# Motercontroller.net
KiCad netlist of a schematic drawn in EAGLE
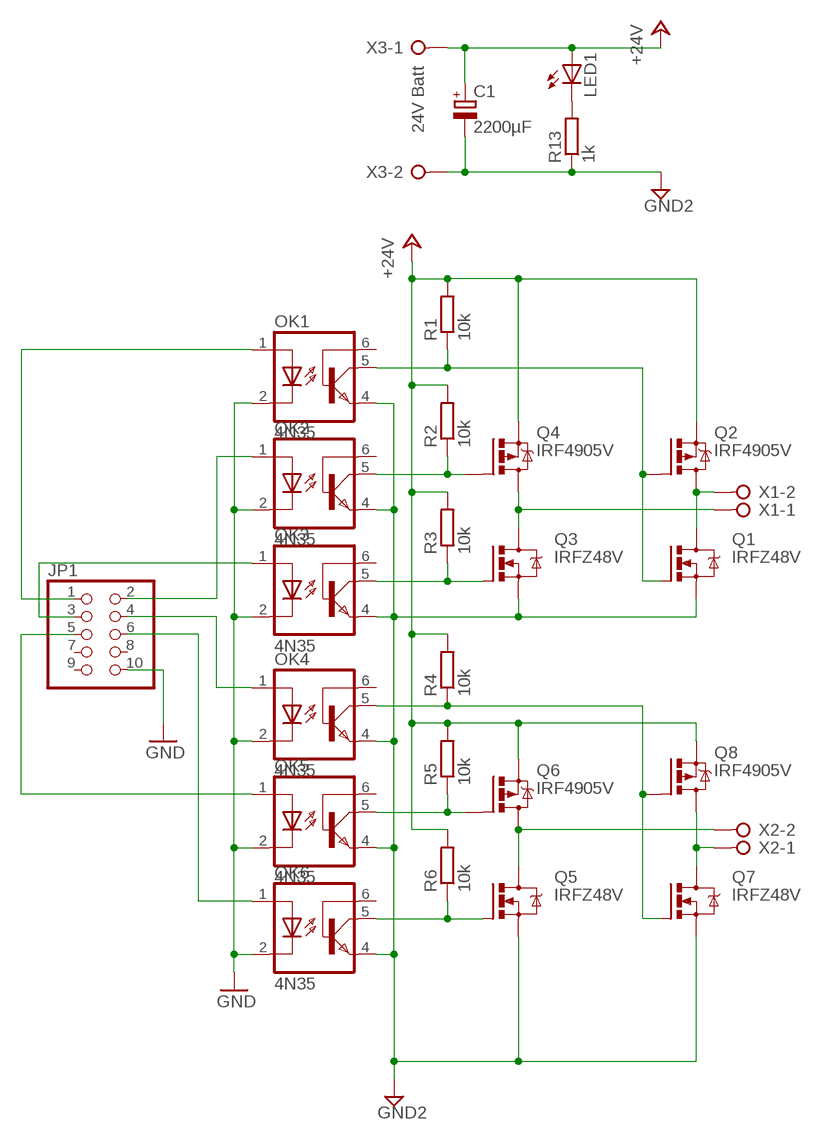
[diagram p0: schematic, sheet 1]

(export (version "E")
  (design (tool "Eeschema 10.0.6"))
  (components
    (comp (ref "C1")
      (value "2200µF")
      (footprint "eagle-import:E5-13")
      (libsource (lib "eagle-import") (part "CPOL-EUE5-13"))
    )
    (comp (ref "JP1")
      (value "PINHD-2X5")
      (footprint "eagle-import:2X05")
      (libsource (lib "eagle-import") (part "PINHD-2X5"))
    )
    (comp (ref "LED1")
      (value "LED5MM")
      (footprint "eagle-import:LED5MM")
      (libsource (lib "eagle-import") (part "LED5MM"))
    )
    (comp (ref "OK1")
      (value "4N35")
      (footprint "eagle-import:DIL06")
      (fields (field (name "MF") "FAIRCHILD SEMICONDUCTOR"))
      (libsource (lib "eagle-import") (part "4N35"))
    )
    (comp (ref "OK2")
      (value "4N35")
      (footprint "eagle-import:DIL06")
      (fields (field (name "MF") "FAIRCHILD SEMICONDUCTOR"))
      (libsource (lib "eagle-import") (part "4N35"))
    )
    (comp (ref "OK3")
      (value "4N35")
      (footprint "eagle-import:DIL06")
      (fields (field (name "MF") "FAIRCHILD SEMICONDUCTOR"))
      (libsource (lib "eagle-import") (part "4N35"))
    )
    (comp (ref "OK4")
      (value "4N35")
      (footprint "eagle-import:DIL06")
      (fields (field (name "MF") "FAIRCHILD SEMICONDUCTOR"))
      (libsource (lib "eagle-import") (part "4N35"))
    )
    (comp (ref "OK5")
      (value "4N35")
      (footprint "eagle-import:DIL06")
      (fields (field (name "MF") "FAIRCHILD SEMICONDUCTOR"))
      (libsource (lib "eagle-import") (part "4N35"))
    )
    (comp (ref "OK6")
      (value "4N35")
      (footprint "eagle-import:DIL06")
      (fields (field (name "MF") "FAIRCHILD SEMICONDUCTOR"))
      (libsource (lib "eagle-import") (part "4N35"))
    )
    (comp (ref "Q1")
      (value "IRFZ48V")
      (footprint "eagle-import:TO220BV")
      (libsource (lib "eagle-import") (part "IRFZ48V"))
    )
    (comp (ref "Q2")
      (value "IRF4905V")
      (footprint "eagle-import:TO220BV")
      (libsource (lib "eagle-import") (part "IRF4905V"))
    )
    (comp (ref "Q3")
      (value "IRFZ48V")
      (footprint "eagle-import:TO220BV")
      (libsource (lib "eagle-import") (part "IRFZ48V"))
    )
    (comp (ref "Q4")
      (value "IRF4905V")
      (footprint "eagle-import:TO220BV")
      (libsource (lib "eagle-import") (part "IRF4905V"))
    )
    (comp (ref "Q5")
      (value "IRFZ48V")
      (footprint "eagle-import:TO220BV")
      (libsource (lib "eagle-import") (part "IRFZ48V"))
    )
    (comp (ref "Q6")
      (value "IRF4905V")
      (footprint "eagle-import:TO220BV")
      (libsource (lib "eagle-import") (part "IRF4905V"))
    )
    (comp (ref "Q7")
      (value "IRFZ48V")
      (footprint "eagle-import:TO220BV")
      (libsource (lib "eagle-import") (part "IRFZ48V"))
    )
    (comp (ref "Q8")
      (value "IRF4905V")
      (footprint "eagle-import:TO220BV")
      (libsource (lib "eagle-import") (part "IRF4905V"))
    )
    (comp (ref "R1")
      (value "10k")
      (footprint "eagle-import:0207_10")
      (libsource (lib "eagle-import") (part "R-EU_0207/10"))
    )
    (comp (ref "R2")
      (value "10k")
      (footprint "eagle-import:0207_10")
      (libsource (lib "eagle-import") (part "R-EU_0207/10"))
    )
    (comp (ref "R3")
      (value "10k")
      (footprint "eagle-import:0207_10")
      (libsource (lib "eagle-import") (part "R-EU_0207/10"))
    )
    (comp (ref "R4")
      (value "10k")
      (footprint "eagle-import:0207_10")
      (libsource (lib "eagle-import") (part "R-EU_0207/10"))
    )
    (comp (ref "R5")
      (value "10k")
      (footprint "eagle-import:0207_10")
      (libsource (lib "eagle-import") (part "R-EU_0207/10"))
    )
    (comp (ref "R6")
      (value "10k")
      (footprint "eagle-import:0207_10")
      (libsource (lib "eagle-import") (part "R-EU_0207/10"))
    )
    (comp (ref "R13")
      (value "1k")
      (footprint "eagle-import:0207_10")
      (libsource (lib "eagle-import") (part "R-EU_0207/10"))
    )
    (comp (ref "X1")
      (value "W237-02P")
      (footprint "eagle-import:W237-132")
      (fields (field (name "OC_FARNELL") "unknown") (field (name "OC_NEWARK") "unknown"))
      (libsource (lib "eagle-import") (part "W237-02P"))
    )
    (comp (ref "X2")
      (value "W237-02P")
      (footprint "eagle-import:W237-132")
      (fields (field (name "OC_FARNELL") "unknown") (field (name "OC_NEWARK") "unknown"))
      (libsource (lib "eagle-import") (part "W237-02P"))
    )
    (comp (ref "X3")
      (value "24V Batt")
      (footprint "eagle-import:W237-132")
      (fields (field (name "OC_FARNELL") "unknown") (field (name "OC_NEWARK") "unknown"))
      (libsource (lib "eagle-import") (part "W237-02P"))
    )
  )
  (nets
    (net (code "1") (name "+24V") (class "Default")
      (node (ref "C1") (pin "+") (pinfunction "+_+") (pintype "passive"))
      (node (ref "LED1") (pin "A") (pinfunction "A_A") (pintype "passive"))
      (node (ref "Q2") (pin "S") (pinfunction "S_S") (pintype "passive"))
      (node (ref "Q4") (pin "S") (pinfunction "S_S") (pintype "passive"))
      (node (ref "Q6") (pin "S") (pinfunction "S_S") (pintype "passive"))
      (node (ref "Q8") (pin "S") (pinfunction "S_S") (pintype "passive"))
      (node (ref "R1") (pin "2") (pinfunction "2_2") (pintype "passive"))
      (node (ref "R2") (pin "2") (pinfunction "2_2") (pintype "passive"))
      (node (ref "R3") (pin "2") (pinfunction "2_2") (pintype "passive"))
      (node (ref "R4") (pin "2") (pinfunction "2_2") (pintype "passive"))
      (node (ref "R5") (pin "2") (pinfunction "2_2") (pintype "passive"))
      (node (ref "R6") (pin "2") (pinfunction "2_2") (pintype "passive"))
      (node (ref "X3") (pin "1") (pinfunction "KL_1") (pintype "passive"))
    )
    (net (code "2") (name "GND") (class "Default")
      (node (ref "JP1") (pin "10") (pinfunction "10_10") (pintype "passive"))
      (node (ref "OK1") (pin "2") (pinfunction "C_2") (pintype "passive"))
      (node (ref "OK2") (pin "2") (pinfunction "C_2") (pintype "passive"))
      (node (ref "OK3") (pin "2") (pinfunction "C_2") (pintype "passive"))
      (node (ref "OK4") (pin "2") (pinfunction "C_2") (pintype "passive"))
      (node (ref "OK5") (pin "2") (pinfunction "C_2") (pintype "passive"))
      (node (ref "OK6") (pin "2") (pinfunction "C_2") (pintype "passive"))
    )
    (net (code "3") (name "GND2") (class "Default")
      (node (ref "C1") (pin "-") (pinfunction "-_-") (pintype "passive"))
      (node (ref "OK1") (pin "4") (pinfunction "EMI_4") (pintype "passive"))
      (node (ref "OK2") (pin "4") (pinfunction "EMI_4") (pintype "passive"))
      (node (ref "OK3") (pin "4") (pinfunction "EMI_4") (pintype "passive"))
      (node (ref "OK4") (pin "4") (pinfunction "EMI_4") (pintype "passive"))
      (node (ref "OK5") (pin "4") (pinfunction "EMI_4") (pintype "passive"))
      (node (ref "OK6") (pin "4") (pinfunction "EMI_4") (pintype "passive"))
      (node (ref "Q1") (pin "S") (pinfunction "S_S") (pintype "passive"))
      (node (ref "Q3") (pin "S") (pinfunction "S_S") (pintype "passive"))
      (node (ref "Q5") (pin "S") (pinfunction "S_S") (pintype "passive"))
      (node (ref "Q7") (pin "S") (pinfunction "S_S") (pintype "passive"))
      (node (ref "R13") (pin "1") (pinfunction "1_1") (pintype "passive"))
      (node (ref "X3") (pin "2") (pinfunction "KL_2") (pintype "passive"))
    )
    (net (code "4") (name "Net-(LED1-C)") (class "Default")
      (node (ref "LED1") (pin "K") (pinfunction "C_K") (pintype "passive"))
      (node (ref "R13") (pin "2") (pinfunction "2_2") (pintype "passive"))
    )
    (net (code "5") (name "Net-(OK1-A)") (class "Default")
      (node (ref "JP1") (pin "1") (pinfunction "1_1") (pintype "passive"))
      (node (ref "OK1") (pin "1") (pinfunction "A_1") (pintype "passive"))
    )
    (net (code "6") (name "Net-(OK1-COL)") (class "Default")
      (node (ref "OK1") (pin "5") (pinfunction "COL_5") (pintype "passive"))
      (node (ref "Q1") (pin "G") (pinfunction "G_G") (pintype "passive"))
      (node (ref "Q2") (pin "G") (pinfunction "G_G") (pintype "passive"))
      (node (ref "R1") (pin "1") (pinfunction "1_1") (pintype "passive"))
    )
    (net (code "7") (name "Net-(OK2-A)") (class "Default")
      (node (ref "JP1") (pin "2") (pinfunction "2_2") (pintype "passive"))
      (node (ref "OK2") (pin "1") (pinfunction "A_1") (pintype "passive"))
    )
    (net (code "8") (name "Net-(OK2-COL)") (class "Default")
      (node (ref "OK2") (pin "5") (pinfunction "COL_5") (pintype "passive"))
      (node (ref "Q4") (pin "G") (pinfunction "G_G") (pintype "passive"))
      (node (ref "R2") (pin "1") (pinfunction "1_1") (pintype "passive"))
    )
    (net (code "9") (name "Net-(OK3-A)") (class "Default")
      (node (ref "JP1") (pin "3") (pinfunction "3_3") (pintype "passive"))
      (node (ref "OK3") (pin "1") (pinfunction "A_1") (pintype "passive"))
    )
    (net (code "10") (name "Net-(OK3-COL)") (class "Default")
      (node (ref "OK3") (pin "5") (pinfunction "COL_5") (pintype "passive"))
      (node (ref "Q3") (pin "G") (pinfunction "G_G") (pintype "passive"))
      (node (ref "R3") (pin "1") (pinfunction "1_1") (pintype "passive"))
    )
    (net (code "11") (name "Net-(OK4-A)") (class "Default")
      (node (ref "JP1") (pin "4") (pinfunction "4_4") (pintype "passive"))
      (node (ref "OK4") (pin "1") (pinfunction "A_1") (pintype "passive"))
    )
    (net (code "12") (name "Net-(OK4-COL)") (class "Default")
      (node (ref "OK4") (pin "5") (pinfunction "COL_5") (pintype "passive"))
      (node (ref "Q7") (pin "G") (pinfunction "G_G") (pintype "passive"))
      (node (ref "Q8") (pin "G") (pinfunction "G_G") (pintype "passive"))
      (node (ref "R4") (pin "1") (pinfunction "1_1") (pintype "passive"))
    )
    (net (code "13") (name "Net-(OK5-A)") (class "Default")
      (node (ref "JP1") (pin "5") (pinfunction "5_5") (pintype "passive"))
      (node (ref "OK5") (pin "1") (pinfunction "A_1") (pintype "passive"))
    )
    (net (code "14") (name "Net-(OK5-COL)") (class "Default")
      (node (ref "OK5") (pin "5") (pinfunction "COL_5") (pintype "passive"))
      (node (ref "Q6") (pin "G") (pinfunction "G_G") (pintype "passive"))
      (node (ref "R5") (pin "1") (pinfunction "1_1") (pintype "passive"))
    )
    (net (code "15") (name "Net-(OK6-A)") (class "Default")
      (node (ref "JP1") (pin "6") (pinfunction "6_6") (pintype "passive"))
      (node (ref "OK6") (pin "1") (pinfunction "A_1") (pintype "passive"))
    )
    (net (code "16") (name "Net-(OK6-COL)") (class "Default")
      (node (ref "OK6") (pin "5") (pinfunction "COL_5") (pintype "passive"))
      (node (ref "Q5") (pin "G") (pinfunction "G_G") (pintype "passive"))
      (node (ref "R6") (pin "1") (pinfunction "1_1") (pintype "passive"))
    )
    (net (code "17") (name "Net-(X1A-KL)") (class "Default")
      (node (ref "Q3") (pin "D") (pinfunction "D_D") (pintype "passive"))
      (node (ref "Q4") (pin "D") (pinfunction "D_D") (pintype "passive"))
      (node (ref "X1") (pin "1") (pinfunction "KL_1") (pintype "passive"))
    )
    (net (code "18") (name "Net-(X1B-KL)") (class "Default")
      (node (ref "Q1") (pin "D") (pinfunction "D_D") (pintype "passive"))
      (node (ref "Q2") (pin "D") (pinfunction "D_D") (pintype "passive"))
      (node (ref "X1") (pin "2") (pinfunction "KL_2") (pintype "passive"))
    )
    (net (code "19") (name "Net-(X2A-KL)") (class "Default")
      (node (ref "Q7") (pin "D") (pinfunction "D_D") (pintype "passive"))
      (node (ref "Q8") (pin "D") (pinfunction "D_D") (pintype "passive"))
      (node (ref "X2") (pin "1") (pinfunction "KL_1") (pintype "passive"))
    )
    (net (code "20") (name "Net-(X2B-KL)") (class "Default")
      (node (ref "Q5") (pin "D") (pinfunction "D_D") (pintype "passive"))
      (node (ref "Q6") (pin "D") (pinfunction "D_D") (pintype "passive"))
      (node (ref "X2") (pin "2") (pinfunction "KL_2") (pintype "passive"))
    )
    (net (code "21") (name "unconnected-(JP1-Pad7)") (class "Default")
      (node (ref "JP1") (pin "7") (pinfunction "7_7") (pintype "passive"))
    )
    (net (code "22") (name "unconnected-(JP1-Pad8)") (class "Default")
      (node (ref "JP1") (pin "8") (pinfunction "8_8") (pintype "passive"))
    )
    (net (code "23") (name "unconnected-(JP1-Pad9)") (class "Default")
      (node (ref "JP1") (pin "9") (pinfunction "9_9") (pintype "passive"))
    )
    (net (code "24") (name "unconnected-(OK1-BAS-Pad6)") (class "Default")
      (node (ref "OK1") (pin "6") (pinfunction "BAS_6") (pintype "passive"))
    )
    (net (code "25") (name "unconnected-(OK2-BAS-Pad6)") (class "Default")
      (node (ref "OK2") (pin "6") (pinfunction "BAS_6") (pintype "passive"))
    )
    (net (code "26") (name "unconnected-(OK3-BAS-Pad6)") (class "Default")
      (node (ref "OK3") (pin "6") (pinfunction "BAS_6") (pintype "passive"))
    )
    (net (code "27") (name "unconnected-(OK4-BAS-Pad6)") (class "Default")
      (node (ref "OK4") (pin "6") (pinfunction "BAS_6") (pintype "passive"))
    )
    (net (code "28") (name "unconnected-(OK5-BAS-Pad6)") (class "Default")
      (node (ref "OK5") (pin "6") (pinfunction "BAS_6") (pintype "passive"))
    )
    (net (code "29") (name "unconnected-(OK6-BAS-Pad6)") (class "Default")
      (node (ref "OK6") (pin "6") (pinfunction "BAS_6") (pintype "passive"))
    )
  )
)
